# SubBoard_V1.net
KiCad netlist of a schematic drawn in EAGLE
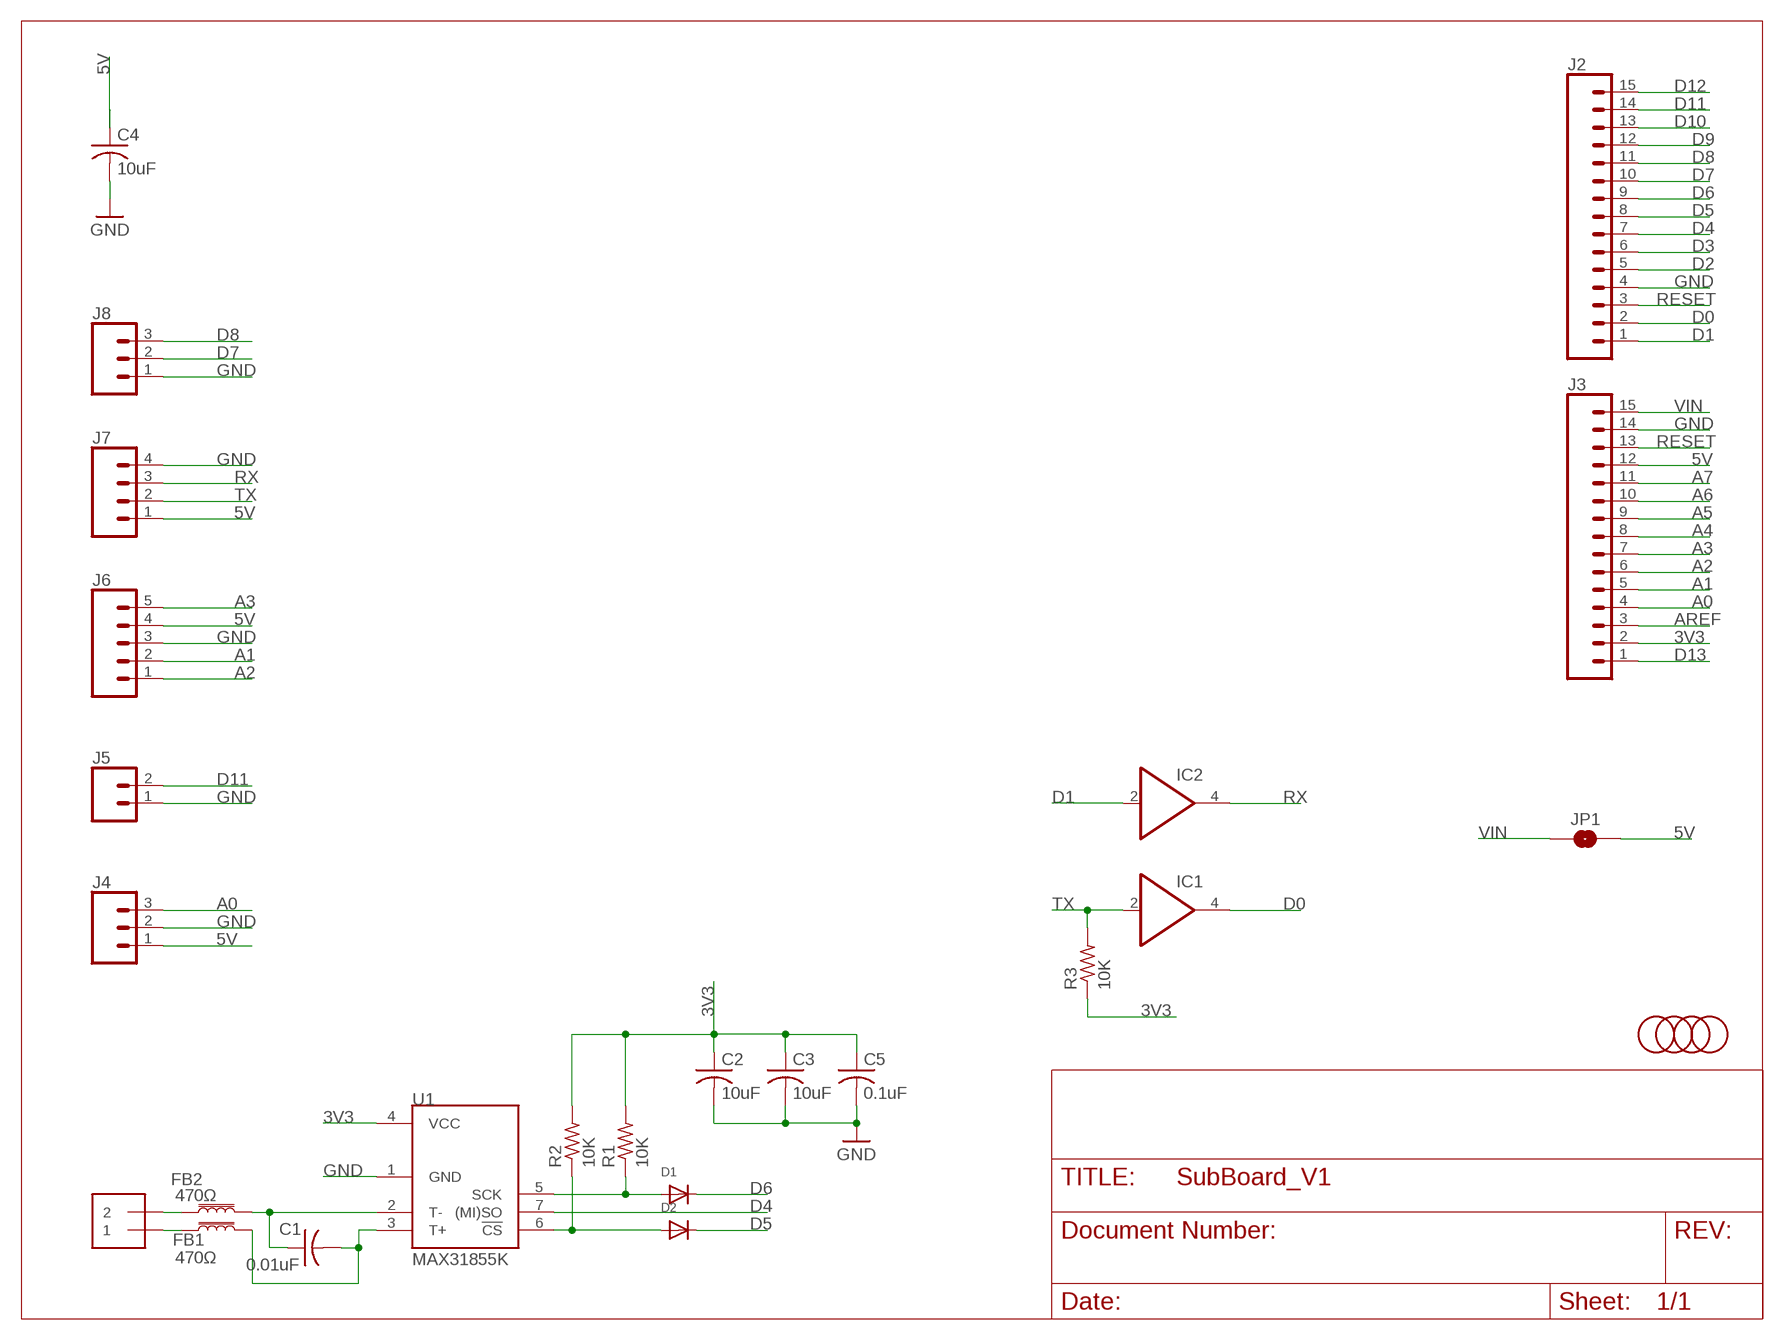
[diagram p0: schematic, sheet 1]

(export (version "E")
  (design (tool "Eeschema 10.0.6"))
  (components
    (comp (ref "C1")
      (value "0.01uF")
      (footprint "eagle-import:C0603")
      (libsource (lib "eagle-import") (part "C-USC0603"))
    )
    (comp (ref "C2")
      (value "10uF")
      (footprint "eagle-import:C0603")
      (libsource (lib "eagle-import") (part "C-USC0603"))
    )
    (comp (ref "C3")
      (value "10uF")
      (footprint "eagle-import:C0603")
      (libsource (lib "eagle-import") (part "C-USC0603"))
    )
    (comp (ref "C4")
      (value "10uF")
      (footprint "eagle-import:C0603")
      (libsource (lib "eagle-import") (part "C-USC0603"))
    )
    (comp (ref "C5")
      (value "0.1uF")
      (footprint "eagle-import:C0603")
      (libsource (lib "eagle-import") (part "C-USC0603"))
    )
    (comp (ref "D1")
      (value "DIODESOD-523")
      (footprint "eagle-import:SOD-523")
      (libsource (lib "eagle-import") (part "DIODESOD-523"))
    )
    (comp (ref "D2")
      (value "DIODESOD-523")
      (footprint "eagle-import:SOD-523")
      (libsource (lib "eagle-import") (part "DIODESOD-523"))
    )
    (comp (ref "FB1")
      (value "470Ω")
      (footprint "eagle-import:0603")
      (libsource (lib "eagle-import") (part "FERRITE_BEAD-0603-470Ω-100MHZ-1A-200MILIΩ"))
    )
    (comp (ref "FB2")
      (value "470Ω")
      (footprint "eagle-import:0603")
      (libsource (lib "eagle-import") (part "FERRITE_BEAD-0603-470Ω-100MHZ-1A-200MILIΩ"))
    )
    (comp (ref "IC1")
      (value "74LVC1G07DBV")
      (footprint "eagle-import:SOT23-5")
      (libsource (lib "eagle-import") (part "741G07DBVLVC"))
    )
    (comp (ref "IC2")
      (value "74LVC1G07DBV")
      (footprint "eagle-import:SOT23-5")
      (libsource (lib "eagle-import") (part "741G07DBVLVC"))
    )
    (comp (ref "J1")
      (value "1X2-3.5MM")
      (footprint "eagle-import:1X2-3.5MM")
      (libsource (lib "eagle-import") (part "1X2-3.5MM"))
    )
    (comp (ref "J2")
      (value "CONN_15")
      (footprint "eagle-import:1X15")
      (libsource (lib "eagle-import") (part "CONN_15"))
    )
    (comp (ref "J3")
      (value "CONN_15")
      (footprint "eagle-import:1X15")
      (libsource (lib "eagle-import") (part "CONN_15"))
    )
    (comp (ref "J4")
      (value "CONN_03JST-PTH")
      (footprint "eagle-import:JST-3-PTH")
      (libsource (lib "eagle-import") (part "CONN_03JST-PTH"))
    )
    (comp (ref "J5")
      (value "CONN_02JST-PTH-2")
      (footprint "eagle-import:JST-2-PTH")
      (libsource (lib "eagle-import") (part "CONN_02JST-PTH-2"))
    )
    (comp (ref "J6")
      (value "CONN_05JST")
      (footprint "eagle-import:JST-5-PTH")
      (libsource (lib "eagle-import") (part "CONN_05JST"))
    )
    (comp (ref "J7")
      (value "CONN_04POLAR")
      (footprint "eagle-import:MOLEX-1X4")
      (libsource (lib "eagle-import") (part "CONN_04POLAR"))
    )
    (comp (ref "J8")
      (value "CONN_03JST-PTH")
      (footprint "eagle-import:JST-3-PTH")
      (libsource (lib "eagle-import") (part "CONN_03JST-PTH"))
    )
    (comp (ref "JP1")
      (value "JUMPER-SMT_2_NO_SILK")
      (footprint "eagle-import:SMT-JUMPER_2_NO_SILK")
      (libsource (lib "eagle-import") (part "JUMPER-SMT_2_NO_SILK"))
    )
    (comp (ref "R1")
      (value "10K")
      (footprint "eagle-import:R0402")
      (libsource (lib "eagle-import") (part "R-US_R0402"))
    )
    (comp (ref "R2")
      (value "10K")
      (footprint "eagle-import:R0402")
      (libsource (lib "eagle-import") (part "R-US_R0402"))
    )
    (comp (ref "R3")
      (value "10K")
      (footprint "eagle-import:R0402")
      (libsource (lib "eagle-import") (part "R-US_R0402"))
    )
    (comp (ref "U$1")
      (value "FIDUCIAL")
      (footprint "eagle-import:FIDUCIAL_1MM")
      (libsource (lib "eagle-import") (part "FIDUCIAL"))
    )
    (comp (ref "U$2")
      (value "FIDUCIAL")
      (footprint "eagle-import:FIDUCIAL_1MM")
      (libsource (lib "eagle-import") (part "FIDUCIAL"))
    )
    (comp (ref "U$3")
      (value "FIDUCIAL")
      (footprint "eagle-import:FIDUCIAL_1MM")
      (libsource (lib "eagle-import") (part "FIDUCIAL"))
    )
    (comp (ref "U$4")
      (value "FIDUCIAL")
      (footprint "eagle-import:FIDUCIAL_1MM")
      (libsource (lib "eagle-import") (part "FIDUCIAL"))
    )
    (comp (ref "U1")
      (value "MAX31855K")
      (footprint "eagle-import:SO08")
      (libsource (lib "eagle-import") (part "MAX31855K"))
    )
  )
  (nets
    (net (code "1") (name "/3V3") (class "Default")
      (node (ref "C2") (pin "1") (pinfunction "1_1") (pintype "passive"))
      (node (ref "C3") (pin "1") (pinfunction "1_1") (pintype "passive"))
      (node (ref "C5") (pin "1") (pinfunction "1_1") (pintype "passive"))
      (node (ref "J3") (pin "2") (pinfunction "2_2") (pintype "passive"))
      (node (ref "R1") (pin "2") (pinfunction "2_2") (pintype "passive"))
      (node (ref "R2") (pin "2") (pinfunction "2_2") (pintype "passive"))
      (node (ref "R3") (pin "1") (pinfunction "1_1") (pintype "passive"))
      (node (ref "U1") (pin "4") (pinfunction "VCC_4") (pintype "bidirectional"))
    )
    (net (code "2") (name "/5V") (class "Default")
      (node (ref "C4") (pin "1") (pinfunction "1_1") (pintype "passive"))
      (node (ref "J3") (pin "12") (pinfunction "12_12") (pintype "passive"))
      (node (ref "J4") (pin "1") (pinfunction "1_1") (pintype "passive"))
      (node (ref "J6") (pin "4") (pinfunction "4_4") (pintype "passive"))
      (node (ref "J7") (pin "1") (pinfunction "1_1") (pintype "passive"))
      (node (ref "JP1") (pin "2") (pinfunction "2_2") (pintype "passive"))
    )
    (net (code "3") (name "/A0") (class "Default")
      (node (ref "J3") (pin "4") (pinfunction "4_4") (pintype "passive"))
      (node (ref "J4") (pin "3") (pinfunction "3_3") (pintype "passive"))
    )
    (net (code "4") (name "/A1") (class "Default")
      (node (ref "J3") (pin "5") (pinfunction "5_5") (pintype "passive"))
      (node (ref "J6") (pin "2") (pinfunction "2_2") (pintype "passive"))
    )
    (net (code "5") (name "/A2") (class "Default")
      (node (ref "J3") (pin "6") (pinfunction "6_6") (pintype "passive"))
      (node (ref "J6") (pin "1") (pinfunction "1_1") (pintype "passive"))
    )
    (net (code "6") (name "/A3") (class "Default")
      (node (ref "J3") (pin "7") (pinfunction "7_7") (pintype "passive"))
      (node (ref "J6") (pin "5") (pinfunction "5_5") (pintype "passive"))
    )
    (net (code "7") (name "/A4") (class "Default")
      (node (ref "J3") (pin "8") (pinfunction "8_8") (pintype "passive"))
    )
    (net (code "8") (name "/A5") (class "Default")
      (node (ref "J3") (pin "9") (pinfunction "9_9") (pintype "passive"))
    )
    (net (code "9") (name "/A6") (class "Default")
      (node (ref "J3") (pin "10") (pinfunction "10_10") (pintype "passive"))
    )
    (net (code "10") (name "/A7") (class "Default")
      (node (ref "J3") (pin "11") (pinfunction "11_11") (pintype "passive"))
    )
    (net (code "11") (name "/AREF") (class "Default")
      (node (ref "J3") (pin "3") (pinfunction "3_3") (pintype "passive"))
    )
    (net (code "12") (name "/D0") (class "Default")
      (node (ref "IC1") (pin "4") (pinfunction "O_4") (pintype "open_collector"))
      (node (ref "J2") (pin "2") (pinfunction "2_2") (pintype "passive"))
    )
    (net (code "13") (name "/D1") (class "Default")
      (node (ref "IC2") (pin "2") (pinfunction "I_2") (pintype "input"))
      (node (ref "J2") (pin "1") (pinfunction "1_1") (pintype "passive"))
    )
    (net (code "14") (name "/D2") (class "Default")
      (node (ref "J2") (pin "5") (pinfunction "5_5") (pintype "passive"))
    )
    (net (code "15") (name "/D3") (class "Default")
      (node (ref "J2") (pin "6") (pinfunction "6_6") (pintype "passive"))
    )
    (net (code "16") (name "/D4") (class "Default")
      (node (ref "J2") (pin "7") (pinfunction "7_7") (pintype "passive"))
      (node (ref "U1") (pin "7") (pinfunction "(MI)SO_7") (pintype "bidirectional"))
    )
    (net (code "17") (name "/D5") (class "Default")
      (node (ref "D2") (pin "K") (pinfunction "C_K") (pintype "passive"))
      (node (ref "J2") (pin "8") (pinfunction "8_8") (pintype "passive"))
    )
    (net (code "18") (name "/D6") (class "Default")
      (node (ref "D1") (pin "K") (pinfunction "C_K") (pintype "passive"))
      (node (ref "J2") (pin "9") (pinfunction "9_9") (pintype "passive"))
    )
    (net (code "19") (name "/D7") (class "Default")
      (node (ref "J2") (pin "10") (pinfunction "10_10") (pintype "passive"))
      (node (ref "J8") (pin "2") (pinfunction "2_2") (pintype "passive"))
    )
    (net (code "20") (name "/D8") (class "Default")
      (node (ref "J2") (pin "11") (pinfunction "11_11") (pintype "passive"))
      (node (ref "J8") (pin "3") (pinfunction "3_3") (pintype "passive"))
    )
    (net (code "21") (name "/D9") (class "Default")
      (node (ref "J2") (pin "12") (pinfunction "12_12") (pintype "passive"))
    )
    (net (code "22") (name "/D10") (class "Default")
      (node (ref "J2") (pin "13") (pinfunction "13_13") (pintype "passive"))
    )
    (net (code "23") (name "/D11") (class "Default")
      (node (ref "J2") (pin "14") (pinfunction "14_14") (pintype "passive"))
      (node (ref "J5") (pin "2") (pinfunction "2_2") (pintype "passive"))
    )
    (net (code "24") (name "/D12") (class "Default")
      (node (ref "J2") (pin "15") (pinfunction "15_15") (pintype "passive"))
    )
    (net (code "25") (name "/D13") (class "Default")
      (node (ref "J3") (pin "1") (pinfunction "1_1") (pintype "passive"))
    )
    (net (code "26") (name "/RESET") (class "Default")
      (node (ref "J2") (pin "3") (pinfunction "3_3") (pintype "passive"))
      (node (ref "J3") (pin "13") (pinfunction "13_13") (pintype "passive"))
    )
    (net (code "27") (name "/RX") (class "Default")
      (node (ref "IC2") (pin "4") (pinfunction "O_4") (pintype "open_collector"))
      (node (ref "J7") (pin "3") (pinfunction "3_3") (pintype "passive"))
    )
    (net (code "28") (name "/TX") (class "Default")
      (node (ref "IC1") (pin "2") (pinfunction "I_2") (pintype "input"))
      (node (ref "J7") (pin "2") (pinfunction "2_2") (pintype "passive"))
      (node (ref "R3") (pin "2") (pinfunction "2_2") (pintype "passive"))
    )
    (net (code "29") (name "/VIN") (class "Default")
      (node (ref "J3") (pin "15") (pinfunction "15_15") (pintype "passive"))
      (node (ref "JP1") (pin "1") (pinfunction "1_1") (pintype "passive"))
    )
    (net (code "30") (name "GND") (class "Default")
      (node (ref "C2") (pin "2") (pinfunction "2_2") (pintype "passive"))
      (node (ref "C3") (pin "2") (pinfunction "2_2") (pintype "passive"))
      (node (ref "C4") (pin "2") (pinfunction "2_2") (pintype "passive"))
      (node (ref "C5") (pin "2") (pinfunction "2_2") (pintype "passive"))
      (node (ref "J2") (pin "4") (pinfunction "4_4") (pintype "passive"))
      (node (ref "J3") (pin "14") (pinfunction "14_14") (pintype "passive"))
      (node (ref "J4") (pin "2") (pinfunction "2_2") (pintype "passive"))
      (node (ref "J5") (pin "1") (pinfunction "1_1") (pintype "passive"))
      (node (ref "J6") (pin "3") (pinfunction "3_3") (pintype "passive"))
      (node (ref "J7") (pin "4") (pinfunction "4_4") (pintype "passive"))
      (node (ref "J8") (pin "1") (pinfunction "1_1") (pintype "passive"))
      (node (ref "U1") (pin "1") (pinfunction "GND_1") (pintype "bidirectional"))
    )
    (net (code "31") (name "Net-(FB1-Pad1)") (class "Default")
      (node (ref "FB1") (pin "1") (pinfunction "1_1") (pintype "passive"))
      (node (ref "J1") (pin "1") (pinfunction "1_1") (pintype "passive"))
    )
    (net (code "32") (name "Net-(FB2-Pad1)") (class "Default")
      (node (ref "FB2") (pin "1") (pinfunction "1_1") (pintype "passive"))
      (node (ref "J1") (pin "2") (pinfunction "2_2") (pintype "passive"))
    )
    (net (code "33") (name "Net-(U1-SCK)") (class "Default")
      (node (ref "D1") (pin "A") (pinfunction "A_A") (pintype "passive"))
      (node (ref "R1") (pin "1") (pinfunction "1_1") (pintype "passive"))
      (node (ref "U1") (pin "5") (pinfunction "SCK_5") (pintype "bidirectional"))
    )
    (net (code "34") (name "Net-(U1-T+)") (class "Default")
      (node (ref "C1") (pin "2") (pinfunction "2_2") (pintype "passive"))
      (node (ref "FB1") (pin "2") (pinfunction "2_2") (pintype "passive"))
      (node (ref "U1") (pin "3") (pinfunction "T+_3") (pintype "bidirectional"))
    )
    (net (code "35") (name "Net-(U1-T-)") (class "Default")
      (node (ref "C1") (pin "1") (pinfunction "1_1") (pintype "passive"))
      (node (ref "FB2") (pin "2") (pinfunction "2_2") (pintype "passive"))
      (node (ref "U1") (pin "2") (pinfunction "T-_2") (pintype "bidirectional"))
    )
    (net (code "36") (name "Net-(U1-~{CS})") (class "Default")
      (node (ref "D2") (pin "A") (pinfunction "A_A") (pintype "passive"))
      (node (ref "R2") (pin "1") (pinfunction "1_1") (pintype "passive"))
      (node (ref "U1") (pin "6") (pinfunction "~{CS}_6") (pintype "bidirectional"))
    )
  )
)
